# SerialCom.net
KiCad netlist of a schematic drawn in Altium Designer
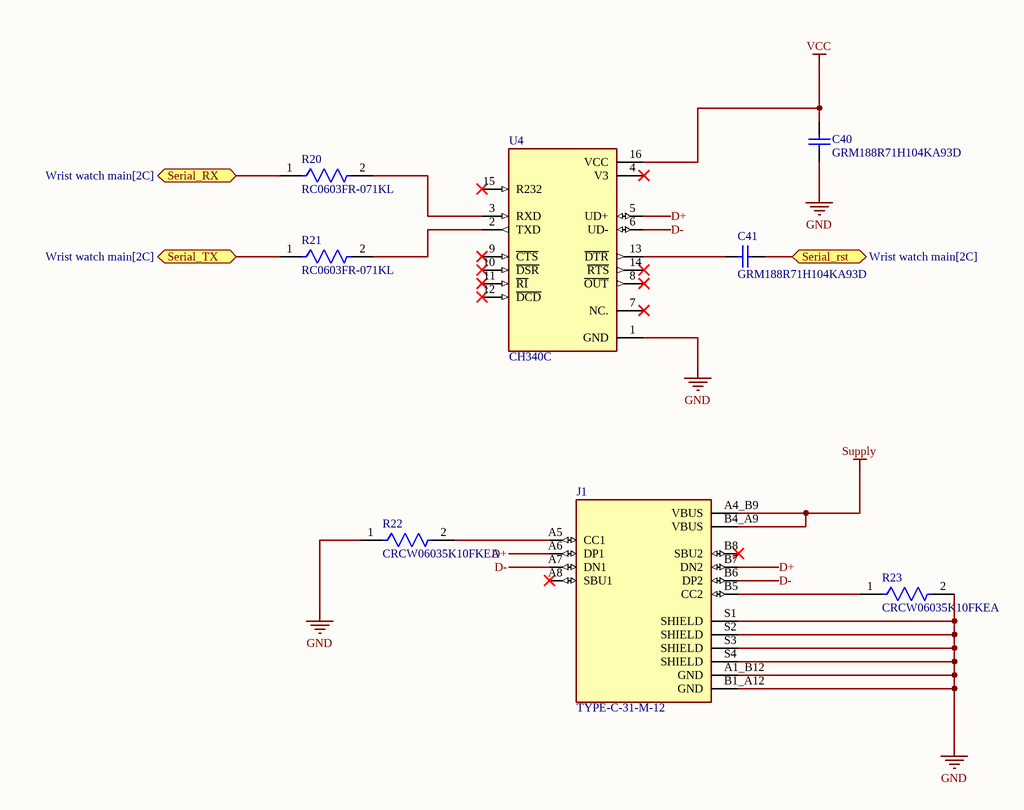
[diagram p0: SerialCom.SchDoc]

(export (version "E")
  (design (tool "Eeschema 10.0.6"))
  (components
    (comp (ref "C40")
      (value "GRM188R71H104KA93D")
      (footprint "CAPC1608X90X35ML10T15")
      (description "Chip Capacitor, 0.1 uF, +/- 10%, 50 V, -55 to 125 degC, 0603 (1608 Metric), RoHS, Tape and Reel")
      (fields (field (name "TOLERANCE") "10%") (field (name "VOLTAGE") "50V"))
      (libsource (lib "Altium Content Vault") (part "CAP-NP-2"))
    )
    (comp (ref "C41")
      (value "GRM188R71H104KA93D")
      (footprint "CAPC1608X90X35ML10T15")
      (description "Chip Capacitor, 0.1 uF, +/- 10%, 50 V, -55 to 125 degC, 0603 (1608 Metric), RoHS, Tape and Reel")
      (fields (field (name "TOLERANCE") "10%") (field (name "VOLTAGE") "50V"))
      (libsource (lib "Altium Content Vault") (part "CAP-NP-2"))
    )
    (comp (ref "J1")
      (value "TYPE-C-31-M-12")
      (footprint "HRO_TYPE-C-31-M-12")
      (description "USB Connectors 24 Receptacle 1 8.94*7.3mm RoHS")
      (fields (field (name "MF") "HRO Electronics Co., Ltd."))
      (libsource (lib "TYPE-C-31-M-12 (1)") (part "TYPE-C-31-M-12"))
    )
    (comp (ref "R20")
      (value "RC0603FR-071KL")
      (footprint "FP-RC0603-0_55-IPC_C")
      (description "RES 1K OHM 1% 1/10W 0603")
      (fields (field (name "TOLERANCE") "1%"))
      (libsource (lib "Altium Content Vault") (part "1029c3af85768c4190bb7ad29bc67b5"))
    )
    (comp (ref "R21")
      (value "RC0603FR-071KL")
      (footprint "FP-RC0603-0_55-IPC_C")
      (description "RES 1K OHM 1% 1/10W 0603")
      (fields (field (name "TOLERANCE") "1%"))
      (libsource (lib "Altium Content Vault") (part "1029c3af85768c4190bb7ad29bc67b5"))
    )
    (comp (ref "R22")
      (value "CRCW06035K10FKEA")
      (footprint "FP-CRCW0603-e3-IPC_C")
      (description "RES Thick Film, 5.1kΩ, 1%, 0.1W, 100ppm/°C, 0603")
      (fields (field (name "TOLERANCE") "1%"))
      (libsource (lib "Altium Content Vault") (part "1029c3af85768c4190bb7ad29bc67b5"))
    )
    (comp (ref "R23")
      (value "CRCW06035K10FKEA")
      (footprint "FP-CRCW0603-e3-IPC_C")
      (description "RES Thick Film, 5.1kΩ, 1%, 0.1W, 100ppm/°C, 0603")
      (fields (field (name "TOLERANCE") "1%"))
      (libsource (lib "Altium Content Vault") (part "1029c3af85768c4190bb7ad29bc67b5"))
    )
    (comp (ref "U4")
      (value "CH340C")
      (footprint "SOIC127P600X180-16N")
      (description "USB to serial chip CH340")
      (fields (field (name "MF") "WCH"))
      (libsource (lib "CH340C (1)") (part "CH340C"))
    )
  )
  (nets
    (net (code "1") (name "/D+") (class "Default")
      (node (ref "J1") (pin "A6") (pinfunction "DP1_A6") (pintype "bidirectional"))
      (node (ref "J1") (pin "B7") (pinfunction "DN2_B7") (pintype "bidirectional"))
      (node (ref "U4") (pin "5") (pinfunction "UD+_5") (pintype "bidirectional"))
    )
    (net (code "2") (name "/D-") (class "Default")
      (node (ref "J1") (pin "A7") (pinfunction "DN1_A7") (pintype "bidirectional"))
      (node (ref "J1") (pin "B6") (pinfunction "DP2_B6") (pintype "bidirectional"))
      (node (ref "U4") (pin "6") (pinfunction "UD-_6") (pintype "bidirectional"))
    )
    (net (code "3") (name "/Serial_RX") (class "Default")
      (node (ref "R20") (pin "1") (pinfunction "1_1") (pintype "passive"))
    )
    (net (code "4") (name "/Serial_TX") (class "Default")
      (node (ref "R21") (pin "1") (pinfunction "1_1") (pintype "passive"))
    )
    (net (code "5") (name "/Serial_rst") (class "Default")
      (node (ref "C41") (pin "2") (pinfunction "2_2") (pintype "passive"))
    )
    (net (code "6") (name "GND") (class "Default")
      (node (ref "C40") (pin "1") (pinfunction "1_1") (pintype "passive"))
      (node (ref "J1") (pin "A1_B12") (pinfunction "GND_A1_B12") (pintype "power_in"))
      (node (ref "J1") (pin "B1_A12") (pinfunction "GND_B1_A12") (pintype "power_in"))
      (node (ref "J1") (pin "S1") (pinfunction "SHIELD_S1") (pintype "passive"))
      (node (ref "J1") (pin "S2") (pinfunction "SHIELD_S2") (pintype "passive"))
      (node (ref "J1") (pin "S3") (pinfunction "SHIELD_S3") (pintype "passive"))
      (node (ref "J1") (pin "S4") (pinfunction "SHIELD_S4") (pintype "passive"))
      (node (ref "R22") (pin "1") (pinfunction "1_1") (pintype "passive"))
      (node (ref "R23") (pin "2") (pinfunction "2_2") (pintype "passive"))
      (node (ref "U4") (pin "1") (pinfunction "GND_1") (pintype "power_in"))
    )
    (net (code "7") (name "Net-(J1-CC1)") (class "Default")
      (node (ref "J1") (pin "A5") (pinfunction "CC1_A5") (pintype "bidirectional"))
      (node (ref "R22") (pin "2") (pinfunction "2_2") (pintype "passive"))
    )
    (net (code "8") (name "Net-(J1-CC2)") (class "Default")
      (node (ref "J1") (pin "B5") (pinfunction "CC2_B5") (pintype "bidirectional"))
      (node (ref "R23") (pin "1") (pinfunction "1_1") (pintype "passive"))
    )
    (net (code "9") (name "Net-(U4-RXD)") (class "Default")
      (node (ref "R20") (pin "2") (pinfunction "2_2") (pintype "passive"))
      (node (ref "U4") (pin "3") (pinfunction "RXD_3") (pintype "input"))
    )
    (net (code "10") (name "Net-(U4-TXD)") (class "Default")
      (node (ref "R21") (pin "2") (pinfunction "2_2") (pintype "passive"))
      (node (ref "U4") (pin "2") (pinfunction "TXD_2") (pintype "output"))
    )
    (net (code "11") (name "Net-(U4-~{DTR})") (class "Default")
      (node (ref "C41") (pin "1") (pinfunction "1_1") (pintype "passive"))
      (node (ref "U4") (pin "13") (pinfunction "~{DTR}_13") (pintype "output"))
    )
    (net (code "12") (name "Supply") (class "Default")
      (node (ref "J1") (pin "A4_B9") (pinfunction "VBUS_A4_B9") (pintype "power_in"))
      (node (ref "J1") (pin "B4_A9") (pinfunction "VBUS_B4_A9") (pintype "power_in"))
    )
    (net (code "13") (name "VCC") (class "Default")
      (node (ref "C40") (pin "2") (pinfunction "2_2") (pintype "passive"))
      (node (ref "U4") (pin "16") (pinfunction "VCC_16") (pintype "power_in"))
    )
    (net (code "14") (name "unconnected-(J1-SBU1-PadA8)") (class "Default")
      (node (ref "J1") (pin "A8") (pinfunction "SBU1_A8") (pintype "bidirectional+no_connect"))
    )
    (net (code "15") (name "unconnected-(J1-SBU2-PadB8)") (class "Default")
      (node (ref "J1") (pin "B8") (pinfunction "SBU2_B8") (pintype "bidirectional+no_connect"))
    )
    (net (code "16") (name "unconnected-(U4-NC.-Pad7)") (class "Default")
      (node (ref "U4") (pin "7") (pinfunction "NC._7") (pintype "passive+no_connect"))
    )
    (net (code "17") (name "unconnected-(U4-R232-Pad15)") (class "Default")
      (node (ref "U4") (pin "15") (pinfunction "R232_15") (pintype "input+no_connect"))
    )
    (net (code "18") (name "unconnected-(U4-V3-Pad4)") (class "Default")
      (node (ref "U4") (pin "4") (pinfunction "V3_4") (pintype "power_in+no_connect"))
    )
    (net (code "19") (name "unconnected-(U4-~{CTS}-Pad9)") (class "Default")
      (node (ref "U4") (pin "9") (pinfunction "~{CTS}_9") (pintype "input+no_connect"))
    )
    (net (code "20") (name "unconnected-(U4-~{DCD}-Pad12)") (class "Default")
      (node (ref "U4") (pin "12") (pinfunction "~{DCD}_12") (pintype "input+no_connect"))
    )
    (net (code "21") (name "unconnected-(U4-~{DSR}-Pad10)") (class "Default")
      (node (ref "U4") (pin "10") (pinfunction "~{DSR}_10") (pintype "input+no_connect"))
    )
    (net (code "22") (name "unconnected-(U4-~{OUT}-Pad8)") (class "Default")
      (node (ref "U4") (pin "8") (pinfunction "~{OUT}_8") (pintype "output+no_connect"))
    )
    (net (code "23") (name "unconnected-(U4-~{RI}-Pad11)") (class "Default")
      (node (ref "U4") (pin "11") (pinfunction "~{RI}_11") (pintype "input+no_connect"))
    )
    (net (code "24") (name "unconnected-(U4-~{RTS}-Pad14)") (class "Default")
      (node (ref "U4") (pin "14") (pinfunction "~{RTS}_14") (pintype "output+no_connect"))
    )
  )
)
